# Sheet6.net
KiCad netlist of a schematic drawn in Altium Designer
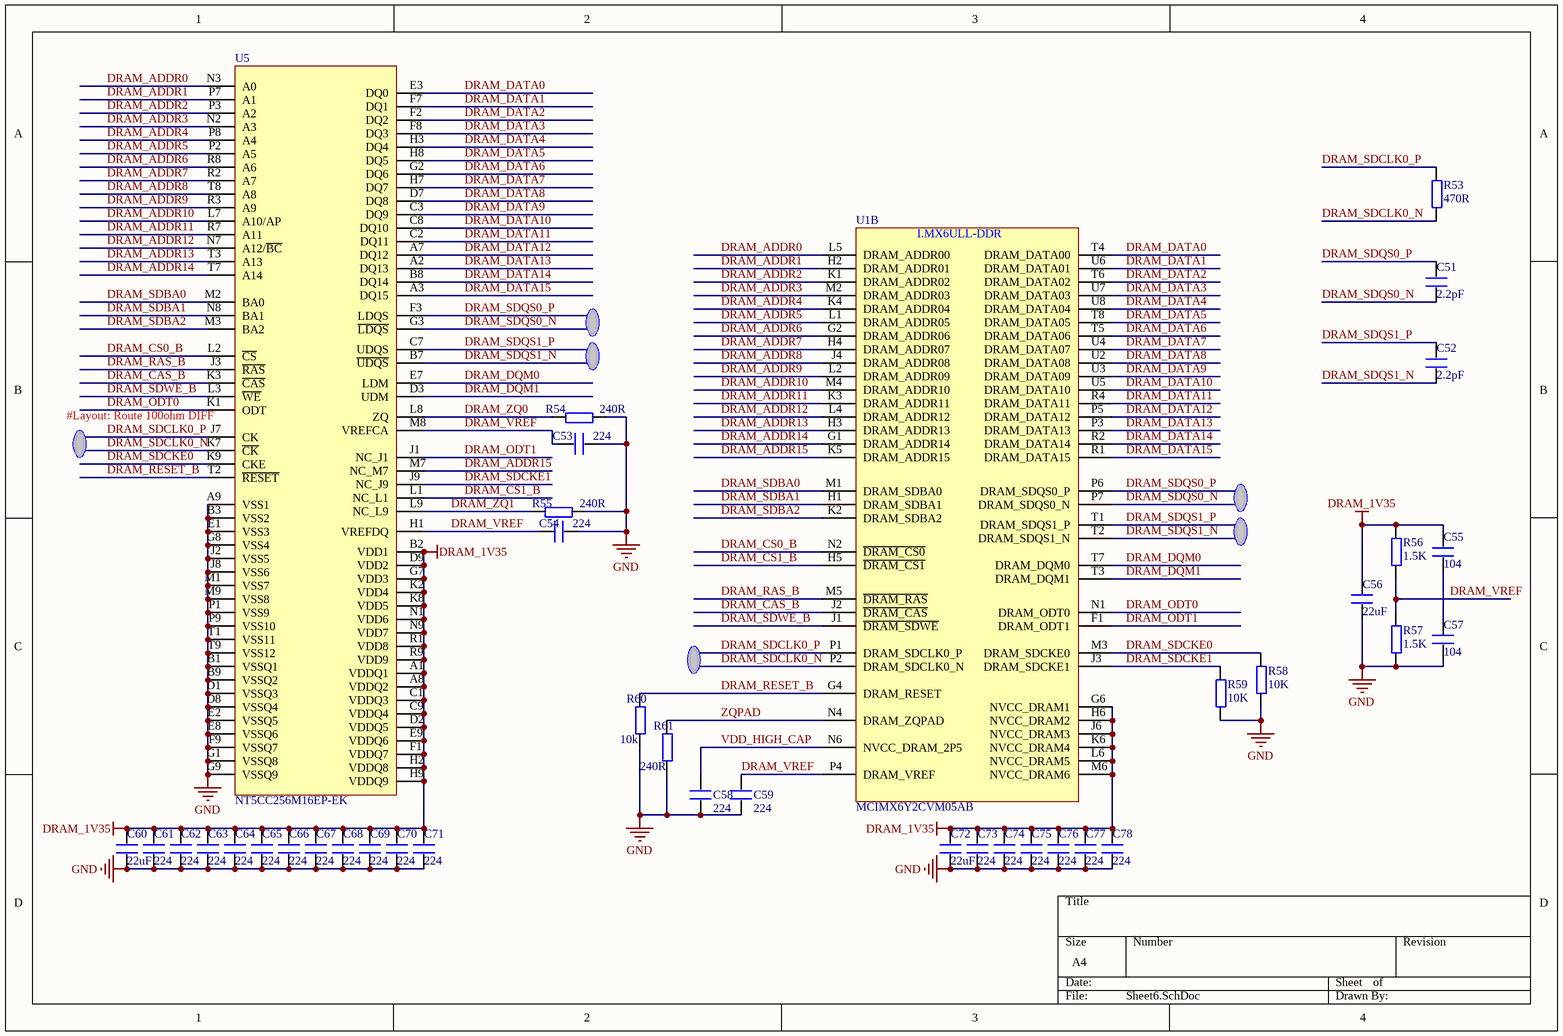
[diagram p0: Sheet6.SchDoc]

(export (version "E")
  (design (tool "Eeschema 10.0.6"))
  (components
    (comp (ref "C51")
      (value "2.2pF")
      (footprint "C 0402")
      (libsource (lib "IMX6ULL_CORE(核心板)_V1.4") (part "C"))
    )
    (comp (ref "C52")
      (value "2.2pF")
      (footprint "C 0402")
      (libsource (lib "IMX6ULL_CORE(核心板)_V1.4") (part "C"))
    )
    (comp (ref "C53")
      (value "224")
      (footprint "C 0402")
      (libsource (lib "IMX6ULL_CORE(核心板)_V1.4") (part "C"))
    )
    (comp (ref "C54")
      (value "224")
      (footprint "C 0402")
      (libsource (lib "IMX6ULL_CORE(核心板)_V1.4") (part "C"))
    )
    (comp (ref "C55")
      (value "104")
      (footprint "C 0402")
      (libsource (lib "IMX6ULL_CORE(核心板)_V1.4") (part "C"))
    )
    (comp (ref "C56")
      (value "22uF")
      (footprint "C 0402")
      (libsource (lib "IMX6ULL_CORE(核心板)_V1.4") (part "C"))
    )
    (comp (ref "C57")
      (value "104")
      (footprint "C 0402")
      (libsource (lib "IMX6ULL_CORE(核心板)_V1.4") (part "C"))
    )
    (comp (ref "C58")
      (value "224")
      (footprint "C 0402")
      (libsource (lib "IMX6ULL_CORE(核心板)_V1.4") (part "C"))
    )
    (comp (ref "C59")
      (value "224")
      (footprint "C 0402")
      (libsource (lib "IMX6ULL_CORE(核心板)_V1.4") (part "C"))
    )
    (comp (ref "C60")
      (value "22uF")
      (footprint "C 0402")
      (libsource (lib "IMX6ULL_CORE(核心板)_V1.4") (part "C"))
    )
    (comp (ref "C61")
      (value "224")
      (footprint "C 0402")
      (libsource (lib "IMX6ULL_CORE(核心板)_V1.4") (part "C"))
    )
    (comp (ref "C62")
      (value "224")
      (footprint "C 0402")
      (libsource (lib "IMX6ULL_CORE(核心板)_V1.4") (part "C"))
    )
    (comp (ref "C63")
      (value "224")
      (footprint "C 0402")
      (libsource (lib "IMX6ULL_CORE(核心板)_V1.4") (part "C"))
    )
    (comp (ref "C64")
      (value "224")
      (footprint "C 0402")
      (libsource (lib "IMX6ULL_CORE(核心板)_V1.4") (part "C"))
    )
    (comp (ref "C65")
      (value "224")
      (footprint "C 0402")
      (libsource (lib "IMX6ULL_CORE(核心板)_V1.4") (part "C"))
    )
    (comp (ref "C66")
      (value "224")
      (footprint "C 0402")
      (libsource (lib "IMX6ULL_CORE(核心板)_V1.4") (part "C"))
    )
    (comp (ref "C67")
      (value "224")
      (footprint "C 0402")
      (libsource (lib "IMX6ULL_CORE(核心板)_V1.4") (part "C"))
    )
    (comp (ref "C68")
      (value "224")
      (footprint "C 0402")
      (libsource (lib "IMX6ULL_CORE(核心板)_V1.4") (part "C"))
    )
    (comp (ref "C69")
      (value "224")
      (footprint "C 0402")
      (libsource (lib "IMX6ULL_CORE(核心板)_V1.4") (part "C"))
    )
    (comp (ref "C70")
      (value "224")
      (footprint "C 0402")
      (libsource (lib "IMX6ULL_CORE(核心板)_V1.4") (part "C"))
    )
    (comp (ref "C71")
      (value "224")
      (footprint "C 0402")
      (libsource (lib "IMX6ULL_CORE(核心板)_V1.4") (part "C"))
    )
    (comp (ref "C72")
      (value "22uF")
      (footprint "C 0402")
      (libsource (lib "IMX6ULL_CORE(核心板)_V1.4") (part "C"))
    )
    (comp (ref "C73")
      (value "224")
      (footprint "C 0402")
      (libsource (lib "IMX6ULL_CORE(核心板)_V1.4") (part "C"))
    )
    (comp (ref "C74")
      (value "224")
      (footprint "C 0402")
      (libsource (lib "IMX6ULL_CORE(核心板)_V1.4") (part "C"))
    )
    (comp (ref "C75")
      (value "224")
      (footprint "C 0402")
      (libsource (lib "IMX6ULL_CORE(核心板)_V1.4") (part "C"))
    )
    (comp (ref "C76")
      (value "224")
      (footprint "C 0402")
      (libsource (lib "IMX6ULL_CORE(核心板)_V1.4") (part "C"))
    )
    (comp (ref "C77")
      (value "224")
      (footprint "C 0402")
      (libsource (lib "IMX6ULL_CORE(核心板)_V1.4") (part "C"))
    )
    (comp (ref "C78")
      (value "224")
      (footprint "C 0402")
      (libsource (lib "IMX6ULL_CORE(核心板)_V1.4") (part "C"))
    )
    (comp (ref "R53")
      (value "470R")
      (footprint "R 0402")
      (libsource (lib "IMX6ULL_CORE(核心板)_V1.4") (part "R"))
    )
    (comp (ref "R54")
      (value "240R")
      (footprint "R 0402")
      (libsource (lib "IMX6ULL_CORE(核心板)_V1.4") (part "R"))
    )
    (comp (ref "R55")
      (value "240R")
      (footprint "R 0402")
      (libsource (lib "IMX6ULL_CORE(核心板)_V1.4") (part "R"))
    )
    (comp (ref "R56")
      (value "1.5K")
      (footprint "R 0402")
      (libsource (lib "IMX6ULL_CORE(核心板)_V1.4") (part "R"))
    )
    (comp (ref "R57")
      (value "1.5K")
      (footprint "R 0402")
      (libsource (lib "IMX6ULL_CORE(核心板)_V1.4") (part "R"))
    )
    (comp (ref "R58")
      (value "10K")
      (footprint "R 0402")
      (libsource (lib "IMX6ULL_CORE(核心板)_V1.4") (part "R"))
    )
    (comp (ref "R59")
      (value "10K")
      (footprint "R 0402")
      (libsource (lib "IMX6ULL_CORE(核心板)_V1.4") (part "R"))
    )
    (comp (ref "R60")
      (value "10k")
      (footprint "R 0402")
      (libsource (lib "IMX6ULL_CORE(核心板)_V1.4") (part "R"))
    )
    (comp (ref "R61")
      (value "240R")
      (footprint "R 0402")
      (libsource (lib "IMX6ULL_CORE(核心板)_V1.4") (part "R"))
    )
    (comp (ref "U1")
      (value "MCIMX6Y2CVM05AB")
      (footprint "BGA289C80P17X17_1400X1400X132")
      (libsource (lib "IMX6ULL_CORE(核心板)_V1.4") (part "MCIMX6Y2CVM05AB"))
    )
    (comp (ref "U5")
      (value "NT5CC256M16EP-EK")
      (footprint "BGA96")
      (libsource (lib "IMX6ULL_CORE(核心板)_V1.4") (part "MT41K256M16TW"))
    )
  )
  (nets
    (net (code "1") (name "/DRAM_ADDR0") (class "Default")
      (node (ref "U1") (pin "L5") (pinfunction "DRAM_ADDR00_L5") (pintype "passive"))
      (node (ref "U5") (pin "N3") (pinfunction "A0_N3") (pintype "passive"))
    )
    (net (code "2") (name "/DRAM_ADDR1") (class "Default")
      (node (ref "U1") (pin "H2") (pinfunction "DRAM_ADDR01_H2") (pintype "passive"))
      (node (ref "U5") (pin "P7") (pinfunction "A1_P7") (pintype "passive"))
    )
    (net (code "3") (name "/DRAM_ADDR2") (class "Default")
      (node (ref "U1") (pin "K1") (pinfunction "DRAM_ADDR02_K1") (pintype "passive"))
      (node (ref "U5") (pin "P3") (pinfunction "A2_P3") (pintype "passive"))
    )
    (net (code "4") (name "/DRAM_ADDR3") (class "Default")
      (node (ref "U1") (pin "M2") (pinfunction "DRAM_ADDR03_M2") (pintype "passive"))
      (node (ref "U5") (pin "N2") (pinfunction "A3_N2") (pintype "passive"))
    )
    (net (code "5") (name "/DRAM_ADDR4") (class "Default")
      (node (ref "U1") (pin "K4") (pinfunction "DRAM_ADDR04_K4") (pintype "passive"))
      (node (ref "U5") (pin "P8") (pinfunction "A4_P8") (pintype "passive"))
    )
    (net (code "6") (name "/DRAM_ADDR5") (class "Default")
      (node (ref "U1") (pin "L1") (pinfunction "DRAM_ADDR05_L1") (pintype "passive"))
      (node (ref "U5") (pin "P2") (pinfunction "A5_P2") (pintype "passive"))
    )
    (net (code "7") (name "/DRAM_ADDR6") (class "Default")
      (node (ref "U1") (pin "G2") (pinfunction "DRAM_ADDR06_G2") (pintype "passive"))
      (node (ref "U5") (pin "R8") (pinfunction "A6_R8") (pintype "passive"))
    )
    (net (code "8") (name "/DRAM_ADDR7") (class "Default")
      (node (ref "U1") (pin "H4") (pinfunction "DRAM_ADDR07_H4") (pintype "passive"))
      (node (ref "U5") (pin "R2") (pinfunction "A7_R2") (pintype "passive"))
    )
    (net (code "9") (name "/DRAM_ADDR8") (class "Default")
      (node (ref "U1") (pin "J4") (pinfunction "DRAM_ADDR08_J4") (pintype "passive"))
      (node (ref "U5") (pin "T8") (pinfunction "A8_T8") (pintype "passive"))
    )
    (net (code "10") (name "/DRAM_ADDR9") (class "Default")
      (node (ref "U1") (pin "L2") (pinfunction "DRAM_ADDR09_L2") (pintype "passive"))
      (node (ref "U5") (pin "R3") (pinfunction "A9_R3") (pintype "passive"))
    )
    (net (code "11") (name "/DRAM_ADDR10") (class "Default")
      (node (ref "U1") (pin "M4") (pinfunction "DRAM_ADDR10_M4") (pintype "passive"))
      (node (ref "U5") (pin "L7") (pinfunction "A10/AP_L7") (pintype "passive"))
    )
    (net (code "12") (name "/DRAM_ADDR11") (class "Default")
      (node (ref "U1") (pin "K3") (pinfunction "DRAM_ADDR11_K3") (pintype "passive"))
      (node (ref "U5") (pin "R7") (pinfunction "A11_R7") (pintype "passive"))
    )
    (net (code "13") (name "/DRAM_ADDR12") (class "Default")
      (node (ref "U1") (pin "L4") (pinfunction "DRAM_ADDR12_L4") (pintype "passive"))
      (node (ref "U5") (pin "N7") (pinfunction "A12/~{BC}_N7") (pintype "passive"))
    )
    (net (code "14") (name "/DRAM_ADDR13") (class "Default")
      (node (ref "U1") (pin "H3") (pinfunction "DRAM_ADDR13_H3") (pintype "passive"))
      (node (ref "U5") (pin "T3") (pinfunction "A13_T3") (pintype "passive"))
    )
    (net (code "15") (name "/DRAM_ADDR14") (class "Default")
      (node (ref "U1") (pin "G1") (pinfunction "DRAM_ADDR14_G1") (pintype "passive"))
      (node (ref "U5") (pin "T7") (pinfunction "A14_T7") (pintype "passive"))
    )
    (net (code "16") (name "/DRAM_ADDR15") (class "Default")
      (node (ref "U1") (pin "K5") (pinfunction "DRAM_ADDR15_K5") (pintype "passive"))
      (node (ref "U5") (pin "M7") (pinfunction "NC_M7_M7") (pintype "passive"))
    )
    (net (code "17") (name "/DRAM_CAS_B") (class "Default")
      (node (ref "U1") (pin "J2") (pinfunction "~{DRAM_CAS}_J2") (pintype "passive"))
      (node (ref "U5") (pin "K3") (pinfunction "~{CAS}_K3") (pintype "passive"))
    )
    (net (code "18") (name "/DRAM_CS0_B") (class "Default")
      (node (ref "U1") (pin "N2") (pinfunction "~{DRAM_CS0}_N2") (pintype "passive"))
      (node (ref "U5") (pin "L2") (pinfunction "~{CS}_L2") (pintype "passive"))
    )
    (net (code "19") (name "/DRAM_CS1_B") (class "Default")
      (node (ref "U1") (pin "H5") (pinfunction "~{DRAM_CS1}_H5") (pintype "passive"))
      (node (ref "U5") (pin "L1") (pinfunction "NC_L1_L1") (pintype "passive"))
    )
    (net (code "20") (name "/DRAM_DATA0") (class "Default")
      (node (ref "U1") (pin "T4") (pinfunction "DRAM_DATA00_T4") (pintype "passive"))
      (node (ref "U5") (pin "E3") (pinfunction "DQ0_E3") (pintype "passive"))
    )
    (net (code "21") (name "/DRAM_DATA1") (class "Default")
      (node (ref "U1") (pin "U6") (pinfunction "DRAM_DATA01_U6") (pintype "passive"))
      (node (ref "U5") (pin "F7") (pinfunction "DQ1_F7") (pintype "passive"))
    )
    (net (code "22") (name "/DRAM_DATA2") (class "Default")
      (node (ref "U1") (pin "T6") (pinfunction "DRAM_DATA02_T6") (pintype "passive"))
      (node (ref "U5") (pin "F2") (pinfunction "DQ2_F2") (pintype "passive"))
    )
    (net (code "23") (name "/DRAM_DATA3") (class "Default")
      (node (ref "U1") (pin "U7") (pinfunction "DRAM_DATA03_U7") (pintype "passive"))
      (node (ref "U5") (pin "F8") (pinfunction "DQ3_F8") (pintype "passive"))
    )
    (net (code "24") (name "/DRAM_DATA4") (class "Default")
      (node (ref "U1") (pin "U8") (pinfunction "DRAM_DATA04_U8") (pintype "passive"))
      (node (ref "U5") (pin "H3") (pinfunction "DQ4_H3") (pintype "passive"))
    )
    (net (code "25") (name "/DRAM_DATA5") (class "Default")
      (node (ref "U1") (pin "T8") (pinfunction "DRAM_DATA05_T8") (pintype "passive"))
      (node (ref "U5") (pin "H8") (pinfunction "DQ5_H8") (pintype "passive"))
    )
    (net (code "26") (name "/DRAM_DATA6") (class "Default")
      (node (ref "U1") (pin "T5") (pinfunction "DRAM_DATA06_T5") (pintype "passive"))
      (node (ref "U5") (pin "G2") (pinfunction "DQ6_G2") (pintype "passive"))
    )
    (net (code "27") (name "/DRAM_DATA7") (class "Default")
      (node (ref "U1") (pin "U4") (pinfunction "DRAM_DATA07_U4") (pintype "passive"))
      (node (ref "U5") (pin "H7") (pinfunction "DQ7_H7") (pintype "passive"))
    )
    (net (code "28") (name "/DRAM_DATA8") (class "Default")
      (node (ref "U1") (pin "U2") (pinfunction "DRAM_DATA08_U2") (pintype "passive"))
      (node (ref "U5") (pin "D7") (pinfunction "DQ8_D7") (pintype "passive"))
    )
    (net (code "29") (name "/DRAM_DATA9") (class "Default")
      (node (ref "U1") (pin "U3") (pinfunction "DRAM_DATA09_U3") (pintype "passive"))
      (node (ref "U5") (pin "C3") (pinfunction "DQ9_C3") (pintype "passive"))
    )
    (net (code "30") (name "/DRAM_DATA10") (class "Default")
      (node (ref "U1") (pin "U5") (pinfunction "DRAM_DATA10_U5") (pintype "passive"))
      (node (ref "U5") (pin "C8") (pinfunction "DQ10_C8") (pintype "passive"))
    )
    (net (code "31") (name "/DRAM_DATA11") (class "Default")
      (node (ref "U1") (pin "R4") (pinfunction "DRAM_DATA11_R4") (pintype "passive"))
      (node (ref "U5") (pin "C2") (pinfunction "DQ11_C2") (pintype "passive"))
    )
    (net (code "32") (name "/DRAM_DATA12") (class "Default")
      (node (ref "U1") (pin "P5") (pinfunction "DRAM_DATA12_P5") (pintype "passive"))
      (node (ref "U5") (pin "A7") (pinfunction "DQ12_A7") (pintype "passive"))
    )
    (net (code "33") (name "/DRAM_DATA13") (class "Default")
      (node (ref "U1") (pin "P3") (pinfunction "DRAM_DATA13_P3") (pintype "passive"))
      (node (ref "U5") (pin "A2") (pinfunction "DQ13_A2") (pintype "passive"))
    )
    (net (code "34") (name "/DRAM_DATA14") (class "Default")
      (node (ref "U1") (pin "R2") (pinfunction "DRAM_DATA14_R2") (pintype "passive"))
      (node (ref "U5") (pin "B8") (pinfunction "DQ14_B8") (pintype "passive"))
    )
    (net (code "35") (name "/DRAM_DATA15") (class "Default")
      (node (ref "U1") (pin "R1") (pinfunction "DRAM_DATA15_R1") (pintype "passive"))
      (node (ref "U5") (pin "A3") (pinfunction "DQ15_A3") (pintype "passive"))
    )
    (net (code "36") (name "/DRAM_DQM0") (class "Default")
      (node (ref "U1") (pin "T7") (pinfunction "DRAM_DQM0_T7") (pintype "passive"))
      (node (ref "U5") (pin "E7") (pinfunction "LDM_E7") (pintype "passive"))
    )
    (net (code "37") (name "/DRAM_DQM1") (class "Default")
      (node (ref "U1") (pin "T3") (pinfunction "DRAM_DQM1_T3") (pintype "passive"))
      (node (ref "U5") (pin "D3") (pinfunction "UDM_D3") (pintype "passive"))
    )
    (net (code "38") (name "/DRAM_ODT0") (class "Default")
      (node (ref "U1") (pin "N1") (pinfunction "DRAM_ODT0_N1") (pintype "passive"))
      (node (ref "U5") (pin "K1") (pinfunction "ODT_K1") (pintype "passive"))
    )
    (net (code "39") (name "/DRAM_ODT1") (class "Default")
      (node (ref "U1") (pin "F1") (pinfunction "DRAM_ODT1_F1") (pintype "passive"))
      (node (ref "U5") (pin "J1") (pinfunction "NC_J1_J1") (pintype "passive"))
    )
    (net (code "40") (name "/DRAM_RAS_B") (class "Default")
      (node (ref "U1") (pin "M5") (pinfunction "~{DRAM_RAS}_M5") (pintype "passive"))
      (node (ref "U5") (pin "J3") (pinfunction "~{RAS}_J3") (pintype "passive"))
    )
    (net (code "41") (name "/DRAM_RESET_B") (class "Default")
      (node (ref "R60") (pin "2") (pintype "passive"))
      (node (ref "U1") (pin "G4") (pinfunction "DRAM_RESET_G4") (pintype "passive"))
      (node (ref "U5") (pin "T2") (pinfunction "~{RESET}_T2") (pintype "passive"))
    )
    (net (code "42") (name "/DRAM_SDBA0") (class "Default")
      (node (ref "U1") (pin "M1") (pinfunction "DRAM_SDBA0_M1") (pintype "passive"))
      (node (ref "U5") (pin "M2") (pinfunction "BA0_M2") (pintype "passive"))
    )
    (net (code "43") (name "/DRAM_SDBA1") (class "Default")
      (node (ref "U1") (pin "H1") (pinfunction "DRAM_SDBA1_H1") (pintype "passive"))
      (node (ref "U5") (pin "N8") (pinfunction "BA1_N8") (pintype "passive"))
    )
    (net (code "44") (name "/DRAM_SDBA2") (class "Default")
      (node (ref "U1") (pin "K2") (pinfunction "DRAM_SDBA2_K2") (pintype "passive"))
      (node (ref "U5") (pin "M3") (pinfunction "BA2_M3") (pintype "passive"))
    )
    (net (code "45") (name "/DRAM_SDCKE0") (class "Default")
      (node (ref "R58") (pin "2") (pintype "passive"))
      (node (ref "U1") (pin "M3") (pinfunction "DRAM_SDCKE0_M3") (pintype "passive"))
      (node (ref "U5") (pin "K9") (pinfunction "CKE_K9") (pintype "passive"))
    )
    (net (code "46") (name "/DRAM_SDCKE1") (class "Default")
      (node (ref "R59") (pin "2") (pintype "passive"))
      (node (ref "U1") (pin "J3") (pinfunction "DRAM_SDCKE1_J3") (pintype "passive"))
      (node (ref "U5") (pin "J9") (pinfunction "NC_J9_J9") (pintype "passive"))
    )
    (net (code "47") (name "/DRAM_SDCLK0_N") (class "Default")
      (node (ref "R53") (pin "1") (pintype "passive"))
      (node (ref "U1") (pin "P2") (pinfunction "DRAM_SDCLK0_N_P2") (pintype "passive"))
      (node (ref "U5") (pin "K7") (pinfunction "~{CK}_K7") (pintype "passive"))
    )
    (net (code "48") (name "/DRAM_SDCLK0_P") (class "Default")
      (node (ref "R53") (pin "2") (pintype "passive"))
      (node (ref "U1") (pin "P1") (pinfunction "DRAM_SDCLK0_P_P1") (pintype "passive"))
      (node (ref "U5") (pin "J7") (pinfunction "CK_J7") (pintype "passive"))
    )
    (net (code "49") (name "/DRAM_SDQS0_N") (class "Default")
      (node (ref "C51") (pin "1") (pintype "passive"))
      (node (ref "U1") (pin "P7") (pinfunction "DRAM_SDQS0_N_P7") (pintype "passive"))
      (node (ref "U5") (pin "G3") (pinfunction "~{LDQS}_G3") (pintype "passive"))
    )
    (net (code "50") (name "/DRAM_SDQS0_P") (class "Default")
      (node (ref "C51") (pin "2") (pintype "passive"))
      (node (ref "U1") (pin "P6") (pinfunction "DRAM_SDQS0_P_P6") (pintype "passive"))
      (node (ref "U5") (pin "F3") (pinfunction "LDQS_F3") (pintype "passive"))
    )
    (net (code "51") (name "/DRAM_SDQS1_N") (class "Default")
      (node (ref "C52") (pin "1") (pintype "passive"))
      (node (ref "U1") (pin "T2") (pinfunction "DRAM_SDQS1_N_T2") (pintype "passive"))
      (node (ref "U5") (pin "B7") (pinfunction "~{UDQS}_B7") (pintype "passive"))
    )
    (net (code "52") (name "/DRAM_SDQS1_P") (class "Default")
      (node (ref "C52") (pin "2") (pintype "passive"))
      (node (ref "U1") (pin "T1") (pinfunction "DRAM_SDQS1_P_T1") (pintype "passive"))
      (node (ref "U5") (pin "C7") (pinfunction "UDQS_C7") (pintype "passive"))
    )
    (net (code "53") (name "/DRAM_SDWE_B") (class "Default")
      (node (ref "U1") (pin "J1") (pinfunction "~{DRAM_SDWE}_J1") (pintype "passive"))
      (node (ref "U5") (pin "L3") (pinfunction "~{WE}_L3") (pintype "passive"))
    )
    (net (code "54") (name "/DRAM_VREF") (class "Default")
      (node (ref "C53") (pin "1") (pintype "passive"))
      (node (ref "C54") (pin "1") (pintype "passive"))
      (node (ref "C59") (pin "2") (pintype "passive"))
      (node (ref "R56") (pin "1") (pintype "passive"))
      (node (ref "R57") (pin "2") (pintype "passive"))
      (node (ref "U1") (pin "P4") (pinfunction "DRAM_VREF_P4") (pintype "passive"))
      (node (ref "U5") (pin "H1") (pinfunction "VREFDQ_H1") (pintype "passive"))
      (node (ref "U5") (pin "M8") (pinfunction "VREFCA_M8") (pintype "passive"))
    )
    (net (code "55") (name "/DRAM_ZQ0") (class "Default")
      (node (ref "R54") (pin "1") (pintype "passive"))
      (node (ref "U5") (pin "L8") (pinfunction "ZQ_L8") (pintype "passive"))
    )
    (net (code "56") (name "/DRAM_ZQ1") (class "Default")
      (node (ref "R55") (pin "1") (pintype "passive"))
      (node (ref "U5") (pin "L9") (pinfunction "NC_L9_L9") (pintype "passive"))
    )
    (net (code "57") (name "/VDD_HIGH_CAP") (class "Default")
      (node (ref "C58") (pin "2") (pintype "passive"))
      (node (ref "U1") (pin "N6") (pinfunction "NVCC_DRAM_2P5_N6") (pintype "passive"))
    )
    (net (code "58") (name "/ZQPAD") (class "Default")
      (node (ref "R61") (pin "2") (pintype "passive"))
      (node (ref "U1") (pin "N4") (pinfunction "DRAM_ZQPAD_N4") (pintype "passive"))
    )
    (net (code "59") (name "DRAM_1V35") (class "Default")
      (node (ref "C55") (pin "2") (pintype "passive"))
      (node (ref "C56") (pin "2") (pintype "passive"))
      (node (ref "C60") (pin "2") (pintype "passive"))
      (node (ref "C61") (pin "2") (pintype "passive"))
      (node (ref "C62") (pin "2") (pintype "passive"))
      (node (ref "C63") (pin "2") (pintype "passive"))
      (node (ref "C64") (pin "2") (pintype "passive"))
      (node (ref "C65") (pin "2") (pintype "passive"))
      (node (ref "C66") (pin "2") (pintype "passive"))
      (node (ref "C67") (pin "2") (pintype "passive"))
      (node (ref "C68") (pin "2") (pintype "passive"))
      (node (ref "C69") (pin "2") (pintype "passive"))
      (node (ref "C70") (pin "2") (pintype "passive"))
      (node (ref "C71") (pin "2") (pintype "passive"))
      (node (ref "C72") (pin "2") (pintype "passive"))
      (node (ref "C73") (pin "2") (pintype "passive"))
      (node (ref "C74") (pin "2") (pintype "passive"))
      (node (ref "C75") (pin "2") (pintype "passive"))
      (node (ref "C76") (pin "2") (pintype "passive"))
      (node (ref "C77") (pin "2") (pintype "passive"))
      (node (ref "C78") (pin "2") (pintype "passive"))
      (node (ref "R56") (pin "2") (pintype "passive"))
      (node (ref "U1") (pin "G6") (pinfunction "NVCC_DRAM1_G6") (pintype "passive"))
      (node (ref "U1") (pin "H6") (pinfunction "NVCC_DRAM2_H6") (pintype "passive"))
      (node (ref "U1") (pin "J6") (pinfunction "NVCC_DRAM3_J6") (pintype "passive"))
      (node (ref "U1") (pin "K6") (pinfunction "NVCC_DRAM4_K6") (pintype "passive"))
      (node (ref "U1") (pin "L6") (pinfunction "NVCC_DRAM5_L6") (pintype "passive"))
      (node (ref "U1") (pin "M6") (pinfunction "NVCC_DRAM6_M6") (pintype "passive"))
      (node (ref "U5") (pin "A1") (pinfunction "VDDQ1_A1") (pintype "passive"))
      (node (ref "U5") (pin "A8") (pinfunction "VDDQ2_A8") (pintype "passive"))
      (node (ref "U5") (pin "B2") (pinfunction "VDD1_B2") (pintype "passive"))
      (node (ref "U5") (pin "C1") (pinfunction "VDDQ3_C1") (pintype "passive"))
      (node (ref "U5") (pin "C9") (pinfunction "VDDQ4_C9") (pintype "passive"))
      (node (ref "U5") (pin "D2") (pinfunction "VDDQ5_D2") (pintype "passive"))
      (node (ref "U5") (pin "D9") (pinfunction "VDD2_D9") (pintype "passive"))
      (node (ref "U5") (pin "E9") (pinfunction "VDDQ6_E9") (pintype "passive"))
      (node (ref "U5") (pin "F1") (pinfunction "VDDQ7_F1") (pintype "passive"))
      (node (ref "U5") (pin "G7") (pinfunction "VDD3_G7") (pintype "passive"))
      (node (ref "U5") (pin "H2") (pinfunction "VDDQ8_H2") (pintype "passive"))
      (node (ref "U5") (pin "H9") (pinfunction "VDDQ9_H9") (pintype "passive"))
      (node (ref "U5") (pin "K2") (pinfunction "VDD4_K2") (pintype "passive"))
      (node (ref "U5") (pin "K8") (pinfunction "VDD5_K8") (pintype "passive"))
      (node (ref "U5") (pin "N1") (pinfunction "VDD6_N1") (pintype "passive"))
      (node (ref "U5") (pin "N9") (pinfunction "VDD7_N9") (pintype "passive"))
      (node (ref "U5") (pin "R1") (pinfunction "VDD8_R1") (pintype "passive"))
      (node (ref "U5") (pin "R9") (pinfunction "VDD9_R9") (pintype "passive"))
    )
    (net (code "60") (name "GND") (class "Default")
      (node (ref "C53") (pin "2") (pintype "passive"))
      (node (ref "C54") (pin "2") (pintype "passive"))
      (node (ref "C56") (pin "1") (pintype "passive"))
      (node (ref "C57") (pin "1") (pintype "passive"))
      (node (ref "C58") (pin "1") (pintype "passive"))
      (node (ref "C59") (pin "1") (pintype "passive"))
      (node (ref "C60") (pin "1") (pintype "passive"))
      (node (ref "C61") (pin "1") (pintype "passive"))
      (node (ref "C62") (pin "1") (pintype "passive"))
      (node (ref "C63") (pin "1") (pintype "passive"))
      (node (ref "C64") (pin "1") (pintype "passive"))
      (node (ref "C65") (pin "1") (pintype "passive"))
      (node (ref "C66") (pin "1") (pintype "passive"))
      (node (ref "C67") (pin "1") (pintype "passive"))
      (node (ref "C68") (pin "1") (pintype "passive"))
      (node (ref "C69") (pin "1") (pintype "passive"))
      (node (ref "C70") (pin "1") (pintype "passive"))
      (node (ref "C71") (pin "1") (pintype "passive"))
      (node (ref "C72") (pin "1") (pintype "passive"))
      (node (ref "C73") (pin "1") (pintype "passive"))
      (node (ref "C74") (pin "1") (pintype "passive"))
      (node (ref "C75") (pin "1") (pintype "passive"))
      (node (ref "C76") (pin "1") (pintype "passive"))
      (node (ref "C77") (pin "1") (pintype "passive"))
      (node (ref "C78") (pin "1") (pintype "passive"))
      (node (ref "R54") (pin "2") (pintype "passive"))
      (node (ref "R55") (pin "2") (pintype "passive"))
      (node (ref "R57") (pin "1") (pintype "passive"))
      (node (ref "R58") (pin "1") (pintype "passive"))
      (node (ref "R59") (pin "1") (pintype "passive"))
      (node (ref "R60") (pin "1") (pintype "passive"))
      (node (ref "R61") (pin "1") (pintype "passive"))
      (node (ref "U5") (pin "A9") (pinfunction "VSS1_A9") (pintype "passive"))
      (node (ref "U5") (pin "B1") (pinfunction "VSSQ1_B1") (pintype "passive"))
      (node (ref "U5") (pin "B3") (pinfunction "VSS2_B3") (pintype "passive"))
      (node (ref "U5") (pin "B9") (pinfunction "VSSQ2_B9") (pintype "passive"))
      (node (ref "U5") (pin "D1") (pinfunction "VSSQ3_D1") (pintype "passive"))
      (node (ref "U5") (pin "D8") (pinfunction "VSSQ4_D8") (pintype "passive"))
      (node (ref "U5") (pin "E1") (pinfunction "VSS3_E1") (pintype "passive"))
      (node (ref "U5") (pin "E2") (pinfunction "VSSQ5_E2") (pintype "passive"))
      (node (ref "U5") (pin "E8") (pinfunction "VSSQ6_E8") (pintype "passive"))
      (node (ref "U5") (pin "F9") (pinfunction "VSSQ7_F9") (pintype "passive"))
      (node (ref "U5") (pin "G1") (pinfunction "VSSQ8_G1") (pintype "passive"))
      (node (ref "U5") (pin "G8") (pinfunction "VSS4_G8") (pintype "passive"))
      (node (ref "U5") (pin "G9") (pinfunction "VSSQ9_G9") (pintype "passive"))
      (node (ref "U5") (pin "J2") (pinfunction "VSS5_J2") (pintype "passive"))
      (node (ref "U5") (pin "J8") (pinfunction "VSS6_J8") (pintype "passive"))
      (node (ref "U5") (pin "M1") (pinfunction "VSS7_M1") (pintype "passive"))
      (node (ref "U5") (pin "M9") (pinfunction "VSS8_M9") (pintype "passive"))
      (node (ref "U5") (pin "P1") (pinfunction "VSS9_P1") (pintype "passive"))
      (node (ref "U5") (pin "P9") (pinfunction "VSS10_P9") (pintype "passive"))
      (node (ref "U5") (pin "T1") (pinfunction "VSS11_T1") (pintype "passive"))
      (node (ref "U5") (pin "T9") (pinfunction "VSS12_T9") (pintype "passive"))
    )
    (net (code "61") (name "Net-(C55-Pad1)") (class "Default")
      (node (ref "C55") (pin "1") (pintype "passive"))
      (node (ref "C57") (pin "2") (pintype "passive"))
    )
  )
)
